# Amplifier.net
KiCad netlist of a schematic drawn in Altium Designer
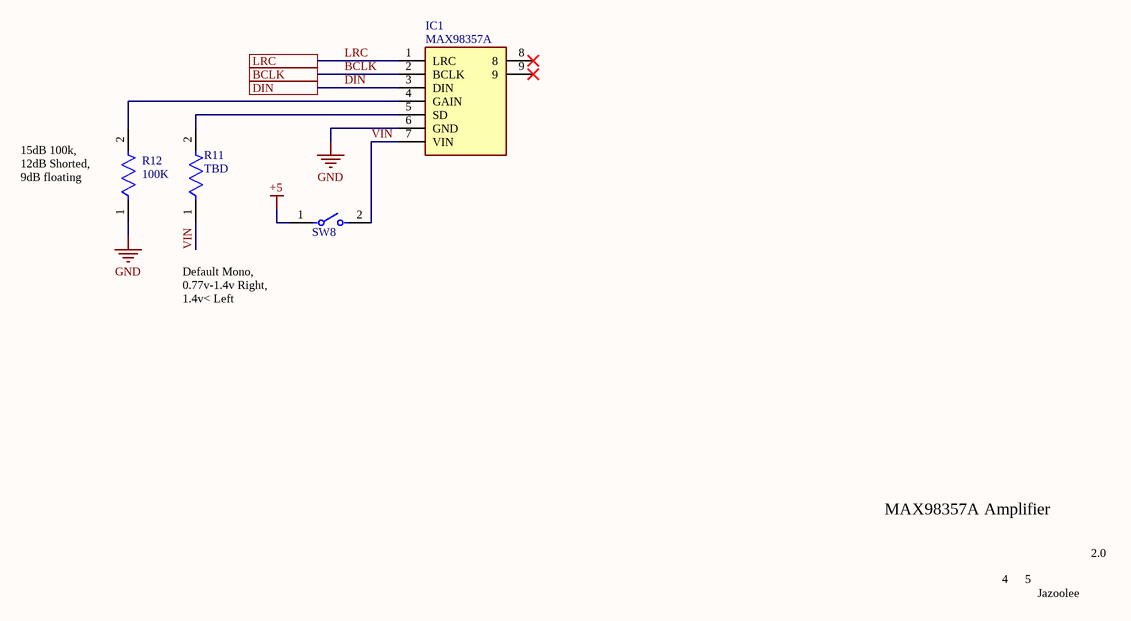
[diagram p0: Amplifier.SchDoc]

(export (version "E")
  (design (tool "Eeschema 10.0.6"))
  (components
    (comp (ref "IC1")
      (value "MAX98357A")
      (footprint "SamacSys:3006")
      (description "Integrated Circuit")
      (fields (field (name "MANUFACTURER_PART_NUMBER") "3006") (field (name "MOUSER PART NUMBER") "485-3006"))
      (libsource (lib "*") (part "3006"))
    )
    (comp (ref "R11")
      (value "TBD")
      (footprint "FP-MRS25-MFG")
      (fields (field (name "TOLERANCE") "1%"))
      (libsource (lib "Altium Content Vault") (part "1029c3af85768c4190bb7ad29bc67b5"))
    )
    (comp (ref "R12")
      (value "ERA-6AEB104V")
      (footprint "FP-ERA6A-IPC_B")
      (description "RES 100K OHM 0.1% 1/8W 0805")
      (fields (field (name "TOLERANCE") "0.1%") (field (name "RESISTANCE") "100K"))
      (libsource (lib "Altium Content Vault") (part "1029c3af85768c4190bb7ad29bc67b5"))
    )
    (comp (ref "SW8")
      (value "BD01")
      (footprint "FP-BD01-MFG")
      (description "SWITCH SLIDE DIP SPST 100MA 5V")
      (libsource (lib "Altium Content Vault") (part "bb27bde45df87f1f469753f287ef5ae"))
    )
  )
  (nets
    (net (code "1") (name "+5") (class "Default")
      (node (ref "SW8") (pin "1") (pinfunction "1_1") (pintype "passive"))
    )
    (net (code "2") (name "/BCLK") (class "Default")
      (node (ref "IC1") (pin "2") (pinfunction "BCLK_2") (pintype "passive"))
    )
    (net (code "3") (name "/DIN") (class "Default")
      (node (ref "IC1") (pin "3") (pinfunction "DIN_3") (pintype "passive"))
    )
    (net (code "4") (name "/LRC") (class "Default")
      (node (ref "IC1") (pin "1") (pinfunction "LRC_1") (pintype "passive"))
    )
    (net (code "5") (name "/VIN") (class "Default")
      (node (ref "IC1") (pin "7") (pinfunction "VIN_7") (pintype "passive"))
      (node (ref "R11") (pin "1") (pinfunction "1_1") (pintype "passive"))
      (node (ref "SW8") (pin "2") (pinfunction "2_2") (pintype "passive"))
    )
    (net (code "6") (name "GND") (class "Default")
      (node (ref "IC1") (pin "6") (pinfunction "GND_6") (pintype "passive"))
      (node (ref "R12") (pin "1") (pinfunction "1_1") (pintype "passive"))
    )
    (net (code "7") (name "Net-(IC1-GAIN)") (class "Default")
      (node (ref "IC1") (pin "4") (pinfunction "GAIN_4") (pintype "passive"))
      (node (ref "R12") (pin "2") (pinfunction "2_2") (pintype "passive"))
    )
    (net (code "8") (name "Net-(IC1-SD)") (class "Default")
      (node (ref "IC1") (pin "5") (pinfunction "SD_5") (pintype "passive"))
      (node (ref "R11") (pin "2") (pinfunction "2_2") (pintype "passive"))
    )
    (net (code "9") (name "unconnected-(IC1-Pad8)") (class "Default")
      (node (ref "IC1") (pin "8") (pinfunction "8_8") (pintype "passive+no_connect"))
    )
    (net (code "10") (name "unconnected-(IC1-Pad9)") (class "Default")
      (node (ref "IC1") (pin "9") (pinfunction "9_9") (pintype "passive+no_connect"))
    )
  )
)
